# TMdojo-Current-Sensor_v0p2.net
KiCad netlist of a schematic drawn in EAGLE
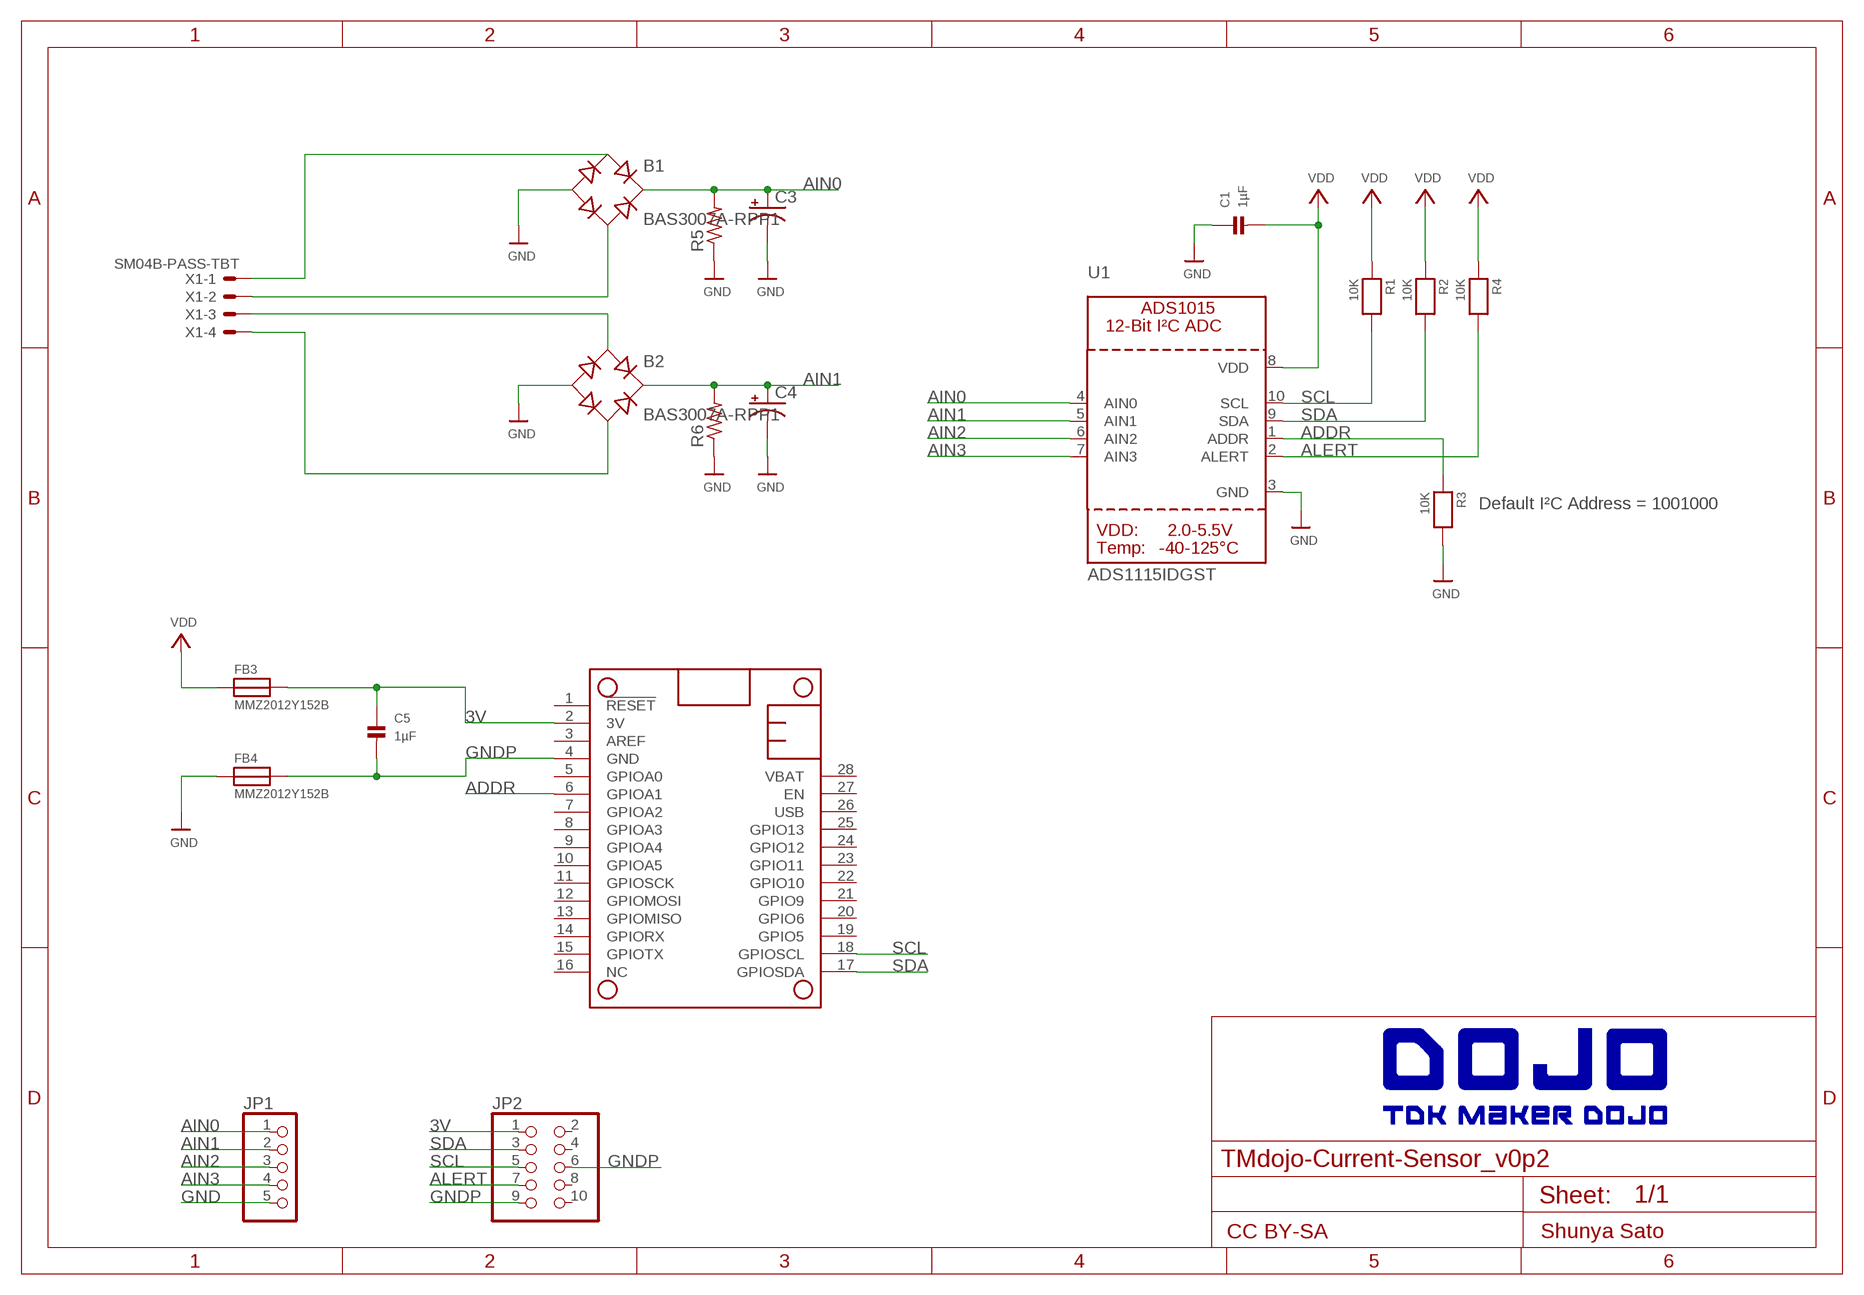
[diagram p0: schematic, sheet 1]

(export (version "E")
  (design (tool "Eeschema 10.0.6"))
  (components
    (comp (ref "B1")
      (value "BAS3007A-RPP1")
      (footprint "eagle-import:SOT143")
      (libsource (lib "eagle-import") (part "BAS3007A-RPP1"))
    )
    (comp (ref "B2")
      (value "BAS3007A-RPP1")
      (footprint "eagle-import:SOT143")
      (libsource (lib "eagle-import") (part "BAS3007A-RPP1"))
    )
    (comp (ref "C1")
      (value "1µF")
      (footprint "eagle-import:0805")
      (libsource (lib "eagle-import") (part "CAP_CERAMIC0805"))
    )
    (comp (ref "C3")
      (value "CPOL-USTT5D7")
      (footprint "eagle-import:TT5D7")
      (libsource (lib "eagle-import") (part "CPOL-USTT5D7"))
    )
    (comp (ref "C4")
      (value "CPOL-USTT5D7")
      (footprint "eagle-import:TT5D7")
      (libsource (lib "eagle-import") (part "CPOL-USTT5D7"))
    )
    (comp (ref "C5")
      (value "1µF")
      (footprint "eagle-import:0805")
      (libsource (lib "eagle-import") (part "CAP_CERAMIC0805"))
    )
    (comp (ref "FB3")
      (value "MMZ2012Y152B")
      (footprint "eagle-import:0805")
      (libsource (lib "eagle-import") (part "FERRITE0805"))
    )
    (comp (ref "FB4")
      (value "MMZ2012Y152B")
      (footprint "eagle-import:0805")
      (libsource (lib "eagle-import") (part "FERRITE0805"))
    )
    (comp (ref "JP1")
      (value "HEADER-1X5ROUND")
      (footprint "eagle-import:1X05_ROUND")
      (libsource (lib "eagle-import") (part "HEADER-1X5ROUND"))
    )
    (comp (ref "JP2")
      (value "HEADER-2X5")
      (footprint "eagle-import:2X05")
      (libsource (lib "eagle-import") (part "HEADER-2X5"))
    )
    (comp (ref "MS1")
      (value "FEATHERWING")
      (footprint "eagle-import:FEATHERWING")
      (libsource (lib "eagle-import") (part "FEATHERWING"))
    )
    (comp (ref "R1")
      (value "10K")
      (footprint "eagle-import:0805")
      (libsource (lib "eagle-import") (part "RESISTOR0805"))
    )
    (comp (ref "R2")
      (value "10K")
      (footprint "eagle-import:0805")
      (libsource (lib "eagle-import") (part "RESISTOR0805"))
    )
    (comp (ref "R3")
      (value "10K")
      (footprint "eagle-import:0805")
      (libsource (lib "eagle-import") (part "RESISTOR0805"))
    )
    (comp (ref "R4")
      (value "10K")
      (footprint "eagle-import:0805")
      (libsource (lib "eagle-import") (part "RESISTOR0805"))
    )
    (comp (ref "R5")
      (value "R-US_FLIPFLOP")
      (footprint "eagle-import:0805-THM")
      (libsource (lib "eagle-import") (part "R-US_FLIPFLOP"))
    )
    (comp (ref "R6")
      (value "R-US_FLIPFLOP")
      (footprint "eagle-import:0805-THM")
      (libsource (lib "eagle-import") (part "R-US_FLIPFLOP"))
    )
    (comp (ref "U1")
      (value "ADS1115IDGST")
      (footprint "eagle-import:MSOP10")
      (libsource (lib "eagle-import") (part "ADC_ADS1015"))
    )
    (comp (ref "X1")
      (value "SM04B-PASS-TBT")
      (footprint "eagle-import:SM04B-PASS-TBT")
      (libsource (lib "eagle-import") (part "SM04B-PASS-TBT"))
    )
  )
  (nets
    (net (code "1") (name "/3V") (class "Default")
      (node (ref "C5") (pin "1") (pinfunction "P$1_1") (pintype "passive"))
      (node (ref "FB3") (pin "2") (pinfunction "P$2_2") (pintype "bidirectional"))
      (node (ref "JP2") (pin "1") (pinfunction "1_1") (pintype "passive"))
      (node (ref "MS1") (pin "2") (pinfunction "3V_2") (pintype "power_in"))
    )
    (net (code "2") (name "/ADDR") (class "Default")
      (node (ref "MS1") (pin "6") (pinfunction "GPIOA1_6") (pintype "bidirectional"))
      (node (ref "R3") (pin "1") (pinfunction "1_1") (pintype "passive"))
      (node (ref "U1") (pin "1") (pinfunction "ADDR_1") (pintype "bidirectional"))
    )
    (net (code "3") (name "/AIN0") (class "Default")
      (node (ref "B1") (pin "+") (pinfunction "+_+") (pintype "passive"))
      (node (ref "C3") (pin "+") (pinfunction "+_+") (pintype "passive"))
      (node (ref "JP1") (pin "1") (pinfunction "1_1") (pintype "passive"))
      (node (ref "R5") (pin "2") (pinfunction "2_2") (pintype "passive"))
      (node (ref "U1") (pin "4") (pinfunction "AIN0_4") (pintype "bidirectional"))
    )
    (net (code "4") (name "/AIN1") (class "Default")
      (node (ref "B2") (pin "+") (pinfunction "+_+") (pintype "passive"))
      (node (ref "C4") (pin "+") (pinfunction "+_+") (pintype "passive"))
      (node (ref "JP1") (pin "2") (pinfunction "2_2") (pintype "passive"))
      (node (ref "R6") (pin "2") (pinfunction "2_2") (pintype "passive"))
      (node (ref "U1") (pin "5") (pinfunction "AIN1_5") (pintype "bidirectional"))
    )
    (net (code "5") (name "/AIN2") (class "Default")
      (node (ref "JP1") (pin "3") (pinfunction "3_3") (pintype "passive"))
      (node (ref "U1") (pin "6") (pinfunction "AIN2_6") (pintype "bidirectional"))
    )
    (net (code "6") (name "/AIN3") (class "Default")
      (node (ref "JP1") (pin "4") (pinfunction "4_4") (pintype "passive"))
      (node (ref "U1") (pin "7") (pinfunction "AIN3_7") (pintype "bidirectional"))
    )
    (net (code "7") (name "/ALERT") (class "Default")
      (node (ref "JP2") (pin "7") (pinfunction "7_7") (pintype "passive"))
      (node (ref "R4") (pin "2") (pinfunction "2_2") (pintype "passive"))
      (node (ref "U1") (pin "2") (pinfunction "ALERT_2") (pintype "bidirectional"))
    )
    (net (code "8") (name "/GNDP") (class "Default")
      (node (ref "C5") (pin "2") (pinfunction "P$2_2") (pintype "passive"))
      (node (ref "FB4") (pin "2") (pinfunction "P$2_2") (pintype "bidirectional"))
      (node (ref "JP2") (pin "6") (pinfunction "6_6") (pintype "passive"))
      (node (ref "JP2") (pin "9") (pinfunction "9_9") (pintype "passive"))
      (node (ref "MS1") (pin "4") (pinfunction "GND_4") (pintype "power_in"))
    )
    (net (code "9") (name "/SCL") (class "Default")
      (node (ref "JP2") (pin "5") (pinfunction "5_5") (pintype "passive"))
      (node (ref "MS1") (pin "18") (pinfunction "GPIOSCL_18") (pintype "bidirectional"))
      (node (ref "R1") (pin "2") (pinfunction "2_2") (pintype "passive"))
      (node (ref "U1") (pin "10") (pinfunction "SCL_10") (pintype "bidirectional"))
    )
    (net (code "10") (name "/SDA") (class "Default")
      (node (ref "JP2") (pin "3") (pinfunction "3_3") (pintype "passive"))
      (node (ref "MS1") (pin "17") (pinfunction "GPIOSDA_17") (pintype "bidirectional"))
      (node (ref "R2") (pin "2") (pinfunction "2_2") (pintype "passive"))
      (node (ref "U1") (pin "9") (pinfunction "SDA_9") (pintype "bidirectional"))
    )
    (net (code "11") (name "/USB") (class "Default")
      (node (ref "MS1") (pin "26") (pinfunction "USB_26") (pintype "power_in"))
    )
    (net (code "12") (name "/VBAT") (class "Default")
      (node (ref "MS1") (pin "28") (pinfunction "VBAT_28") (pintype "power_in"))
    )
    (net (code "13") (name "GND") (class "Default")
      (node (ref "B1") (pin "-") (pinfunction "-_-") (pintype "passive"))
      (node (ref "B2") (pin "-") (pinfunction "-_-") (pintype "passive"))
      (node (ref "C1") (pin "1") (pinfunction "P$1_1") (pintype "passive"))
      (node (ref "C3") (pin "-") (pinfunction "-_-") (pintype "passive"))
      (node (ref "C4") (pin "-") (pinfunction "-_-") (pintype "passive"))
      (node (ref "FB4") (pin "1") (pinfunction "P$1_1") (pintype "bidirectional"))
      (node (ref "JP1") (pin "5") (pinfunction "5_5") (pintype "passive"))
      (node (ref "R3") (pin "2") (pinfunction "2_2") (pintype "passive"))
      (node (ref "R5") (pin "1") (pinfunction "1_1") (pintype "passive"))
      (node (ref "R6") (pin "1") (pinfunction "1_1") (pintype "passive"))
      (node (ref "U1") (pin "3") (pinfunction "GND_3") (pintype "bidirectional"))
    )
    (net (code "14") (name "Net-(B1-AC1)") (class "Default")
      (node (ref "B1") (pin "~1") (pinfunction "AC1_~1") (pintype "passive"))
      (node (ref "X1") (pin "1") (pinfunction "S_1") (pintype "passive"))
    )
    (net (code "15") (name "Net-(B1-AC2)") (class "Default")
      (node (ref "B1") (pin "~2") (pinfunction "AC2_~2") (pintype "passive"))
      (node (ref "X1") (pin "2") (pinfunction "S_2") (pintype "passive"))
    )
    (net (code "16") (name "Net-(B2-AC1)") (class "Default")
      (node (ref "B2") (pin "~1") (pinfunction "AC1_~1") (pintype "passive"))
      (node (ref "X1") (pin "3") (pinfunction "S_3") (pintype "passive"))
    )
    (net (code "17") (name "Net-(B2-AC2)") (class "Default")
      (node (ref "B2") (pin "~2") (pinfunction "AC2_~2") (pintype "passive"))
      (node (ref "X1") (pin "4") (pinfunction "S_4") (pintype "passive"))
    )
    (net (code "18") (name "VDD") (class "Default")
      (node (ref "C1") (pin "2") (pinfunction "P$2_2") (pintype "passive"))
      (node (ref "FB3") (pin "1") (pinfunction "P$1_1") (pintype "bidirectional"))
      (node (ref "R1") (pin "1") (pinfunction "1_1") (pintype "passive"))
      (node (ref "R2") (pin "1") (pinfunction "1_1") (pintype "passive"))
      (node (ref "R4") (pin "1") (pinfunction "1_1") (pintype "passive"))
      (node (ref "U1") (pin "8") (pinfunction "VDD_8") (pintype "bidirectional"))
    )
    (net (code "19") (name "unconnected-(JP2-Pad2)") (class "Default")
      (node (ref "JP2") (pin "2") (pinfunction "2_2") (pintype "passive"))
    )
    (net (code "20") (name "unconnected-(JP2-Pad4)") (class "Default")
      (node (ref "JP2") (pin "4") (pinfunction "4_4") (pintype "passive"))
    )
    (net (code "21") (name "unconnected-(JP2-Pad8)") (class "Default")
      (node (ref "JP2") (pin "8") (pinfunction "8_8") (pintype "passive"))
    )
    (net (code "22") (name "unconnected-(JP2-Pad10)") (class "Default")
      (node (ref "JP2") (pin "10") (pinfunction "10_10") (pintype "passive"))
    )
    (net (code "23") (name "unconnected-(MS1-AREF-Pad3)") (class "Default")
      (node (ref "MS1") (pin "3") (pinfunction "AREF_3") (pintype "passive"))
    )
    (net (code "24") (name "unconnected-(MS1-EN-Pad27)") (class "Default")
      (node (ref "MS1") (pin "27") (pinfunction "EN_27") (pintype "passive"))
    )
    (net (code "25") (name "unconnected-(MS1-GPIO5-Pad19)") (class "Default")
      (node (ref "MS1") (pin "19") (pinfunction "GPIO5_19") (pintype "bidirectional"))
    )
    (net (code "26") (name "unconnected-(MS1-GPIO6-Pad20)") (class "Default")
      (node (ref "MS1") (pin "20") (pinfunction "GPIO6_20") (pintype "bidirectional"))
    )
    (net (code "27") (name "unconnected-(MS1-GPIO9-Pad21)") (class "Default")
      (node (ref "MS1") (pin "21") (pinfunction "GPIO9_21") (pintype "bidirectional"))
    )
    (net (code "28") (name "unconnected-(MS1-GPIO10-Pad22)") (class "Default")
      (node (ref "MS1") (pin "22") (pinfunction "GPIO10_22") (pintype "bidirectional"))
    )
    (net (code "29") (name "unconnected-(MS1-GPIO11-Pad23)") (class "Default")
      (node (ref "MS1") (pin "23") (pinfunction "GPIO11_23") (pintype "bidirectional"))
    )
    (net (code "30") (name "unconnected-(MS1-GPIO12-Pad24)") (class "Default")
      (node (ref "MS1") (pin "24") (pinfunction "GPIO12_24") (pintype "bidirectional"))
    )
    (net (code "31") (name "unconnected-(MS1-GPIO13-Pad25)") (class "Default")
      (node (ref "MS1") (pin "25") (pinfunction "GPIO13_25") (pintype "bidirectional"))
    )
    (net (code "32") (name "unconnected-(MS1-GPIOA0-Pad5)") (class "Default")
      (node (ref "MS1") (pin "5") (pinfunction "GPIOA0_5") (pintype "bidirectional"))
    )
    (net (code "33") (name "unconnected-(MS1-GPIOA2-Pad7)") (class "Default")
      (node (ref "MS1") (pin "7") (pinfunction "GPIOA2_7") (pintype "bidirectional"))
    )
    (net (code "34") (name "unconnected-(MS1-GPIOA3-Pad8)") (class "Default")
      (node (ref "MS1") (pin "8") (pinfunction "GPIOA3_8") (pintype "bidirectional"))
    )
    (net (code "35") (name "unconnected-(MS1-GPIOA4-Pad9)") (class "Default")
      (node (ref "MS1") (pin "9") (pinfunction "GPIOA4_9") (pintype "bidirectional"))
    )
    (net (code "36") (name "unconnected-(MS1-GPIOA5-Pad10)") (class "Default")
      (node (ref "MS1") (pin "10") (pinfunction "GPIOA5_10") (pintype "bidirectional"))
    )
    (net (code "37") (name "unconnected-(MS1-GPIOMISO-Pad13)") (class "Default")
      (node (ref "MS1") (pin "13") (pinfunction "GPIOMISO_13") (pintype "bidirectional"))
    )
    (net (code "38") (name "unconnected-(MS1-GPIOMOSI-Pad12)") (class "Default")
      (node (ref "MS1") (pin "12") (pinfunction "GPIOMOSI_12") (pintype "bidirectional"))
    )
    (net (code "39") (name "unconnected-(MS1-GPIORX-Pad14)") (class "Default")
      (node (ref "MS1") (pin "14") (pinfunction "GPIORX_14") (pintype "bidirectional"))
    )
    (net (code "40") (name "unconnected-(MS1-GPIOSCK-Pad11)") (class "Default")
      (node (ref "MS1") (pin "11") (pinfunction "GPIOSCK_11") (pintype "bidirectional"))
    )
    (net (code "41") (name "unconnected-(MS1-GPIOTX-Pad15)") (class "Default")
      (node (ref "MS1") (pin "15") (pinfunction "GPIOTX_15") (pintype "bidirectional"))
    )
    (net (code "42") (name "unconnected-(MS1-NC-Pad16)") (class "Default")
      (node (ref "MS1") (pin "16") (pinfunction "NC_16") (pintype "passive"))
    )
    (net (code "43") (name "unconnected-(MS1-~{RESET}-Pad1)") (class "Default")
      (node (ref "MS1") (pin "1") (pinfunction "~{RESET}_1") (pintype "input"))
    )
  )
)
